# Control.net
KiCad netlist of a schematic drawn in EAGLE
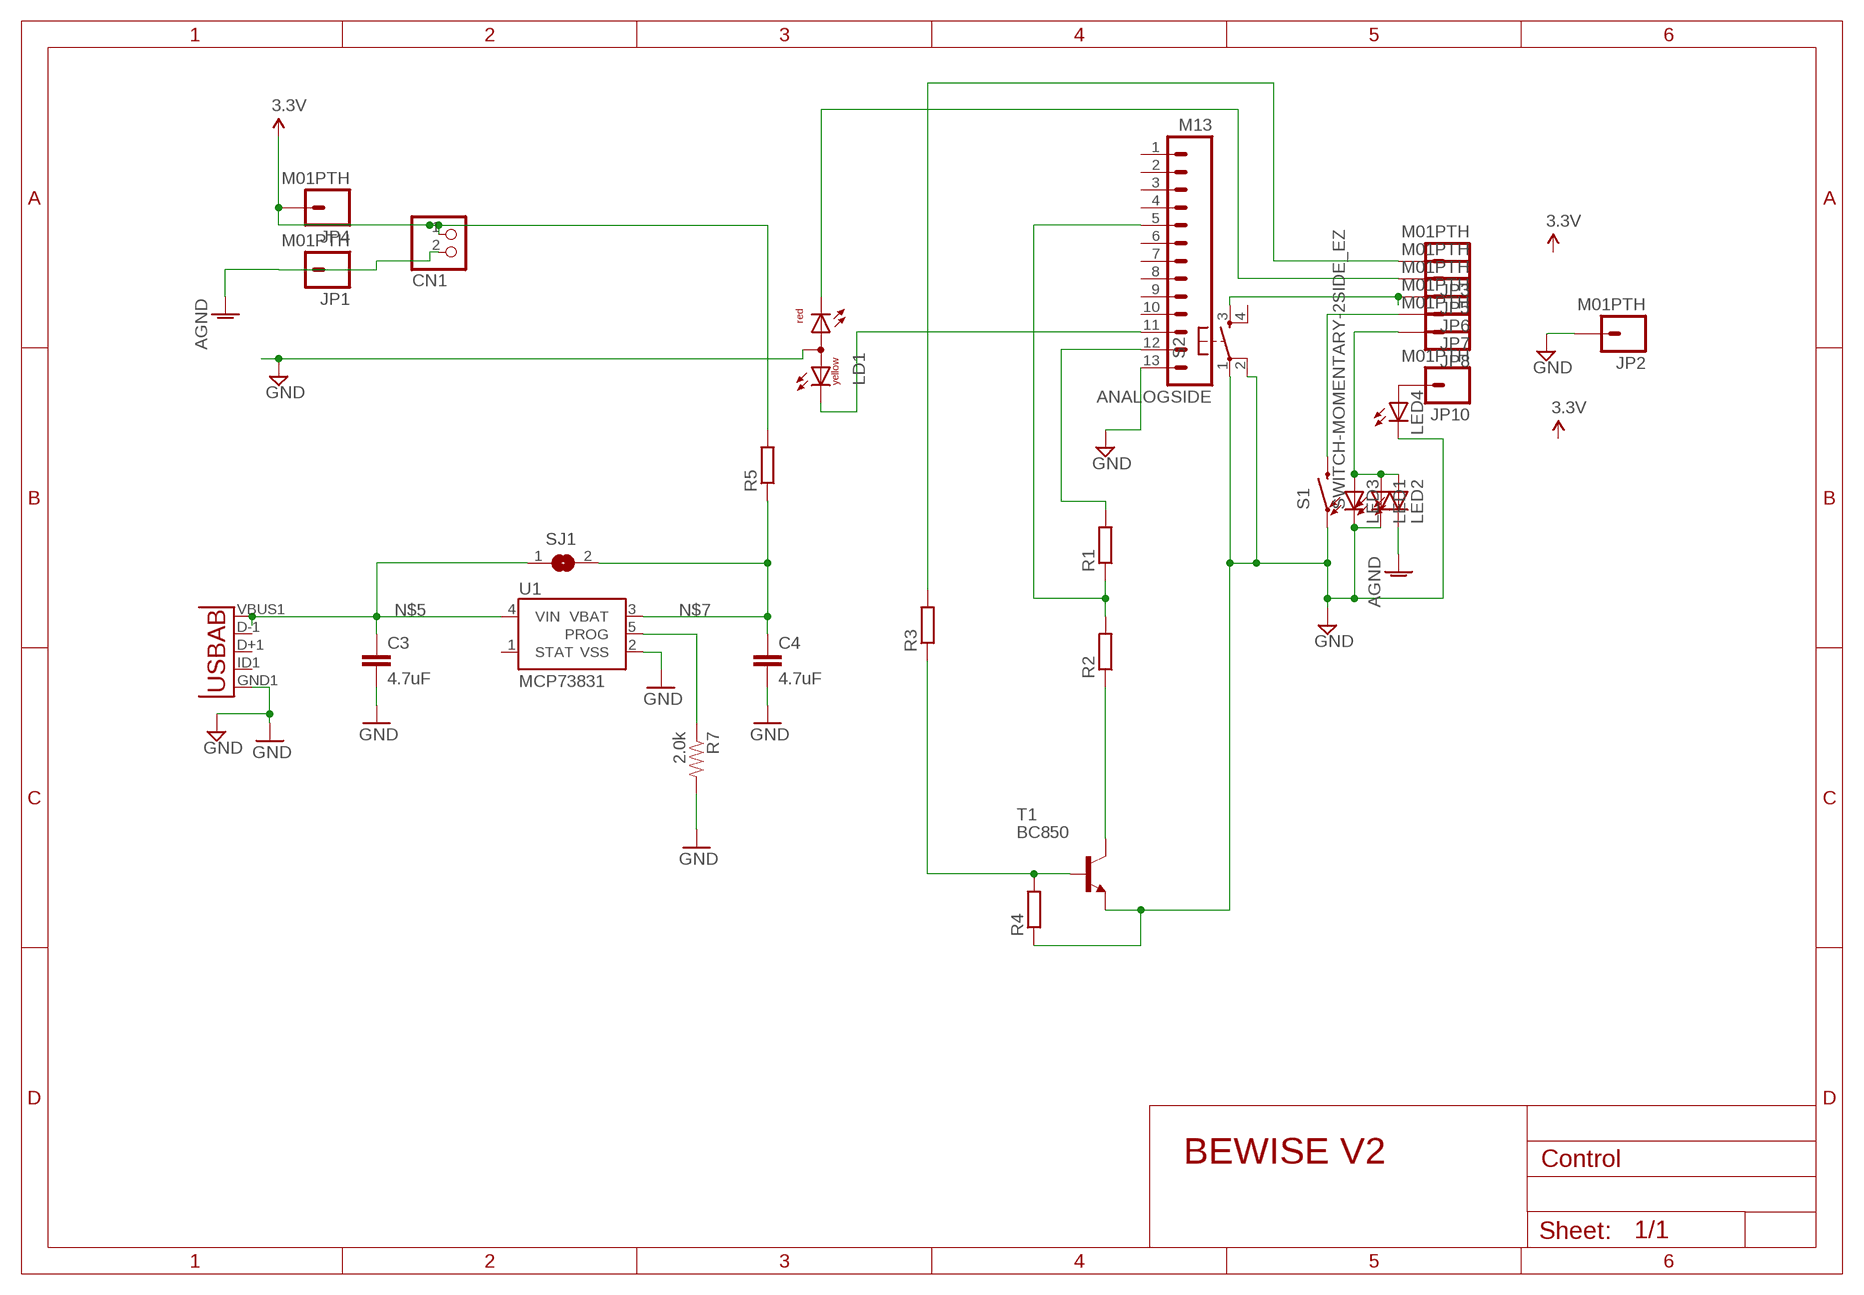
[diagram p0: schematic, sheet 1]

(export (version "E")
  (design (tool "Eeschema 10.0.6"))
  (components
    (comp (ref "ANALOGSIDE")
      (value "M13")
      (footprint "eagle-import:1X13")
      (libsource (lib "eagle-import") (part "M13"))
    )
    (comp (ref "C3")
      (value "4.7uF")
      (footprint "eagle-import:0603-CAP")
      (libsource (lib "eagle-import") (part "4.7UF-6.3V-10%(0603)0603"))
    )
    (comp (ref "C4")
      (value "4.7uF")
      (footprint "eagle-import:0603-CAP")
      (libsource (lib "eagle-import") (part "4.7UF-6.3V-10%(0603)0603"))
    )
    (comp (ref "CN1")
      (value "JST_2PIN-SMT")
      (footprint "eagle-import:JST-PH-2-SMT")
      (libsource (lib "eagle-import") (part "JST_2PIN-SMT"))
    )
    (comp (ref "JP1")
      (value "M01PTH")
      (footprint "eagle-import:1X01")
      (libsource (lib "eagle-import") (part "M01PTH"))
    )
    (comp (ref "JP2")
      (value "M01PTH")
      (footprint "eagle-import:1X01")
      (libsource (lib "eagle-import") (part "M01PTH"))
    )
    (comp (ref "JP3")
      (value "M01PTH")
      (footprint "eagle-import:1X01")
      (libsource (lib "eagle-import") (part "M01PTH"))
    )
    (comp (ref "JP4")
      (value "M01PTH")
      (footprint "eagle-import:1X01")
      (libsource (lib "eagle-import") (part "M01PTH"))
    )
    (comp (ref "JP5")
      (value "M01PTH")
      (footprint "eagle-import:1X01")
      (libsource (lib "eagle-import") (part "M01PTH"))
    )
    (comp (ref "JP6")
      (value "M01PTH")
      (footprint "eagle-import:1X01")
      (libsource (lib "eagle-import") (part "M01PTH"))
    )
    (comp (ref "JP7")
      (value "M01PTH")
      (footprint "eagle-import:1X01")
      (libsource (lib "eagle-import") (part "M01PTH"))
    )
    (comp (ref "JP8")
      (value "M01PTH")
      (footprint "eagle-import:1X01")
      (libsource (lib "eagle-import") (part "M01PTH"))
    )
    (comp (ref "JP9")
      (value "Micro USB")
      (footprint "eagle-import:USB-AB-MICRO-SMD_V03")
      (libsource (lib "eagle-import") (part "USB-ABCONN-11794"))
    )
    (comp (ref "JP10")
      (value "M01PTH")
      (footprint "eagle-import:1X01")
      (libsource (lib "eagle-import") (part "M01PTH"))
    )
    (comp (ref "LD1")
      (value "DUOLED-RY-A")
      (footprint "eagle-import:DUOLED-A-5MM")
      (libsource (lib "eagle-import") (part "DUOLED-RY-A"))
    )
    (comp (ref "LED1")
      (value "LED3MM")
      (footprint "eagle-import:LED3MM")
      (libsource (lib "eagle-import") (part "LED3MM"))
    )
    (comp (ref "LED2")
      (value "LED3MM")
      (footprint "eagle-import:LED3MM")
      (libsource (lib "eagle-import") (part "LED3MM"))
    )
    (comp (ref "LED3")
      (value "LED3MM")
      (footprint "eagle-import:LED3MM")
      (libsource (lib "eagle-import") (part "LED3MM"))
    )
    (comp (ref "LED4")
      (value "LED3MM")
      (footprint "eagle-import:LED3MM")
      (libsource (lib "eagle-import") (part "LED3MM"))
    )
    (comp (ref "R1")
      (value "R-EU_0204/7")
      (footprint "eagle-import:0204_7")
      (libsource (lib "eagle-import") (part "R-EU_0204/7"))
    )
    (comp (ref "R2")
      (value "R-EU_0204/7")
      (footprint "eagle-import:0204_7")
      (libsource (lib "eagle-import") (part "R-EU_0204/7"))
    )
    (comp (ref "R3")
      (value "R-EU_M1206")
      (footprint "eagle-import:M1206")
      (libsource (lib "eagle-import") (part "R-EU_M1206"))
    )
    (comp (ref "R4")
      (value "R-EU_M1206")
      (footprint "eagle-import:M1206")
      (libsource (lib "eagle-import") (part "R-EU_M1206"))
    )
    (comp (ref "R5")
      (value "R-EU_M1206")
      (footprint "eagle-import:M1206")
      (libsource (lib "eagle-import") (part "R-EU_M1206"))
    )
    (comp (ref "R7")
      (value "2.0k")
      (footprint "eagle-import:0603-RES")
      (libsource (lib "eagle-import") (part "2.0KOHM1/10W5%(0603)"))
    )
    (comp (ref "S1")
      (value "SWITCH-MOMENTARY-2SIDE_EZ")
      (footprint "eagle-import:TACTILE-PTH-SIDEEZ")
      (libsource (lib "eagle-import") (part "SWITCH-MOMENTARY-2SIDE_EZ"))
    )
    (comp (ref "S2")
      (value "TAC_SWITCHPTH")
      (footprint "eagle-import:TACTILE-PTH")
      (libsource (lib "eagle-import") (part "TAC_SWITCHPTH"))
    )
    (comp (ref "SJ1") (value "SJ") (footprint "eagle-import:SJ") (libsource (lib "eagle-import") (part "SJ")))
    (comp (ref "T1")
      (value "BC850")
      (footprint "eagle-import:SOT23")
      (libsource (lib "eagle-import") (part "BC850"))
    )
    (comp (ref "U1")
      (value "MCP73831")
      (footprint "eagle-import:SOT23-5")
      (libsource (lib "eagle-import") (part "MCP73831"))
    )
  )
  (nets
    (net (code "1") (name "/N$5") (class "Default")
      (node (ref "C3") (pin "1") (pinfunction "1_1") (pintype "passive"))
      (node (ref "JP9") (pin "VBUS1") (pinfunction "VBUS_VBUS1") (pintype "bidirectional"))
      (node (ref "SJ1") (pin "1") (pinfunction "1_1") (pintype "passive"))
      (node (ref "U1") (pin "4") (pinfunction "VIN_4") (pintype "power_in"))
    )
    (net (code "2") (name "/N$7") (class "Default")
      (node (ref "C4") (pin "1") (pinfunction "1_1") (pintype "passive"))
      (node (ref "R5") (pin "1") (pinfunction "1_1") (pintype "passive"))
      (node (ref "SJ1") (pin "2") (pinfunction "2_2") (pintype "passive"))
      (node (ref "U1") (pin "3") (pinfunction "VBAT_3") (pintype "power_in"))
    )
    (net (code "3") (name "3.3V") (class "Default")
      (node (ref "CN1") (pin "1") (pinfunction "2_1") (pintype "passive"))
      (node (ref "JP4") (pin "1") (pinfunction "1_1") (pintype "passive"))
      (node (ref "R5") (pin "2") (pinfunction "2_2") (pintype "passive"))
    )
    (net (code "4") (name "AGND") (class "Default")
      (node (ref "CN1") (pin "2") (pinfunction "1_2") (pintype "passive"))
      (node (ref "JP1") (pin "1") (pinfunction "1_1") (pintype "passive"))
      (node (ref "LED2") (pin "K") (pinfunction "C_K") (pintype "passive"))
    )
    (net (code "5") (name "GND") (class "Default")
      (node (ref "ANALOGSIDE") (pin "13") (pinfunction "13_13") (pintype "passive"))
      (node (ref "C3") (pin "2") (pinfunction "2_2") (pintype "passive"))
      (node (ref "C4") (pin "2") (pinfunction "2_2") (pintype "passive"))
      (node (ref "JP2") (pin "1") (pinfunction "1_1") (pintype "passive"))
      (node (ref "JP9") (pin "GND1") (pinfunction "GND_GND1") (pintype "bidirectional"))
      (node (ref "LD1") (pin "A") (pinfunction "A_A") (pintype "passive"))
      (node (ref "LED1") (pin "K") (pinfunction "C_K") (pintype "passive"))
      (node (ref "LED3") (pin "K") (pinfunction "C_K") (pintype "passive"))
      (node (ref "LED4") (pin "K") (pinfunction "C_K") (pintype "passive"))
      (node (ref "R4") (pin "1") (pinfunction "1_1") (pintype "passive"))
      (node (ref "R7") (pin "2") (pinfunction "2_2") (pintype "passive"))
      (node (ref "S1") (pin "1") (pinfunction "1_1") (pintype "passive"))
      (node (ref "S2") (pin "1") (pinfunction "1_1") (pintype "passive"))
      (node (ref "S2") (pin "2") (pinfunction "2_2") (pintype "passive"))
      (node (ref "T1") (pin "2") (pinfunction "E_2") (pintype "passive"))
      (node (ref "U1") (pin "2") (pinfunction "VSS_2") (pintype "power_in"))
    )
    (net (code "6") (name "Net-(ANALOGSIDE-Pad5)") (class "Default")
      (node (ref "ANALOGSIDE") (pin "5") (pinfunction "5_5") (pintype "passive"))
      (node (ref "R1") (pin "1") (pinfunction "1_1") (pintype "passive"))
      (node (ref "R2") (pin "2") (pinfunction "2_2") (pintype "passive"))
    )
    (net (code "7") (name "Net-(ANALOGSIDE-Pad12)") (class "Default")
      (node (ref "ANALOGSIDE") (pin "12") (pinfunction "12_12") (pintype "passive"))
      (node (ref "R1") (pin "2") (pinfunction "2_2") (pintype "passive"))
    )
    (net (code "8") (name "Net-(JP3-Pad1)") (class "Default")
      (node (ref "JP3") (pin "1") (pinfunction "1_1") (pintype "passive"))
      (node (ref "R3") (pin "2") (pinfunction "2_2") (pintype "passive"))
    )
    (net (code "9") (name "Net-(JP5-Pad1)") (class "Default")
      (node (ref "JP5") (pin "1") (pinfunction "1_1") (pintype "passive"))
      (node (ref "LD1") (pin "CR") (pinfunction "CR_CR") (pintype "passive"))
    )
    (net (code "10") (name "Net-(JP6-Pad1)") (class "Default")
      (node (ref "JP6") (pin "1") (pinfunction "1_1") (pintype "passive"))
      (node (ref "S2") (pin "3") (pinfunction "3_3") (pintype "passive"))
    )
    (net (code "11") (name "Net-(JP7-Pad1)") (class "Default")
      (node (ref "JP7") (pin "1") (pinfunction "1_1") (pintype "passive"))
      (node (ref "S1") (pin "2") (pinfunction "2_2") (pintype "passive"))
    )
    (net (code "12") (name "Net-(JP8-Pad1)") (class "Default")
      (node (ref "JP8") (pin "1") (pinfunction "1_1") (pintype "passive"))
      (node (ref "LED1") (pin "A") (pinfunction "A_A") (pintype "passive"))
      (node (ref "LED2") (pin "A") (pinfunction "A_A") (pintype "passive"))
      (node (ref "LED3") (pin "A") (pinfunction "A_A") (pintype "passive"))
    )
    (net (code "13") (name "Net-(JP10-Pad1)") (class "Default")
      (node (ref "JP10") (pin "1") (pinfunction "1_1") (pintype "passive"))
      (node (ref "LED4") (pin "A") (pinfunction "A_A") (pintype "passive"))
    )
    (net (code "14") (name "Net-(LD1-CY)") (class "Default")
      (node (ref "ANALOGSIDE") (pin "11") (pinfunction "11_11") (pintype "passive"))
      (node (ref "LD1") (pin "CX") (pinfunction "CY_CX") (pintype "passive"))
    )
    (net (code "15") (name "Net-(T1-B)") (class "Default")
      (node (ref "R3") (pin "1") (pinfunction "1_1") (pintype "passive"))
      (node (ref "R4") (pin "2") (pinfunction "2_2") (pintype "passive"))
      (node (ref "T1") (pin "1") (pinfunction "B_1") (pintype "passive"))
    )
    (net (code "16") (name "Net-(T1-C)") (class "Default")
      (node (ref "R2") (pin "1") (pinfunction "1_1") (pintype "passive"))
      (node (ref "T1") (pin "3") (pinfunction "C_3") (pintype "passive"))
    )
    (net (code "17") (name "Net-(U1-PROG)") (class "Default")
      (node (ref "R7") (pin "1") (pinfunction "1_1") (pintype "passive"))
      (node (ref "U1") (pin "5") (pinfunction "PROG_5") (pintype "input"))
    )
    (net (code "18") (name "unconnected-(ANALOGSIDE-Pad1)") (class "Default")
      (node (ref "ANALOGSIDE") (pin "1") (pinfunction "1_1") (pintype "passive"))
    )
    (net (code "19") (name "unconnected-(ANALOGSIDE-Pad2)") (class "Default")
      (node (ref "ANALOGSIDE") (pin "2") (pinfunction "2_2") (pintype "passive"))
    )
    (net (code "20") (name "unconnected-(ANALOGSIDE-Pad3)") (class "Default")
      (node (ref "ANALOGSIDE") (pin "3") (pinfunction "3_3") (pintype "passive"))
    )
    (net (code "21") (name "unconnected-(ANALOGSIDE-Pad4)") (class "Default")
      (node (ref "ANALOGSIDE") (pin "4") (pinfunction "4_4") (pintype "passive"))
    )
    (net (code "22") (name "unconnected-(ANALOGSIDE-Pad6)") (class "Default")
      (node (ref "ANALOGSIDE") (pin "6") (pinfunction "6_6") (pintype "passive"))
    )
    (net (code "23") (name "unconnected-(ANALOGSIDE-Pad7)") (class "Default")
      (node (ref "ANALOGSIDE") (pin "7") (pinfunction "7_7") (pintype "passive"))
    )
    (net (code "24") (name "unconnected-(ANALOGSIDE-Pad8)") (class "Default")
      (node (ref "ANALOGSIDE") (pin "8") (pinfunction "8_8") (pintype "passive"))
    )
    (net (code "25") (name "unconnected-(ANALOGSIDE-Pad9)") (class "Default")
      (node (ref "ANALOGSIDE") (pin "9") (pinfunction "9_9") (pintype "passive"))
    )
    (net (code "26") (name "unconnected-(ANALOGSIDE-Pad10)") (class "Default")
      (node (ref "ANALOGSIDE") (pin "10") (pinfunction "10_10") (pintype "passive"))
    )
    (net (code "27") (name "unconnected-(JP9-D+-PadD+1)") (class "Default")
      (node (ref "JP9") (pin "D+1") (pinfunction "D+_D+1") (pintype "bidirectional"))
    )
    (net (code "28") (name "unconnected-(JP9-D--PadD-1)") (class "Default")
      (node (ref "JP9") (pin "D-1") (pinfunction "D-_D-1") (pintype "bidirectional"))
    )
    (net (code "29") (name "unconnected-(JP9-USBID-PadID1)") (class "Default")
      (node (ref "JP9") (pin "ID1") (pinfunction "USBID_ID1") (pintype "bidirectional"))
    )
    (net (code "30") (name "unconnected-(S2-Pad4)") (class "Default")
      (node (ref "S2") (pin "4") (pinfunction "4_4") (pintype "passive"))
    )
    (net (code "31") (name "unconnected-(U1-STAT-Pad1)") (class "Default")
      (node (ref "U1") (pin "1") (pinfunction "STAT_1") (pintype "output"))
    )
  )
)
